# relay_board.net
KiCad netlist of a schematic drawn in EAGLE
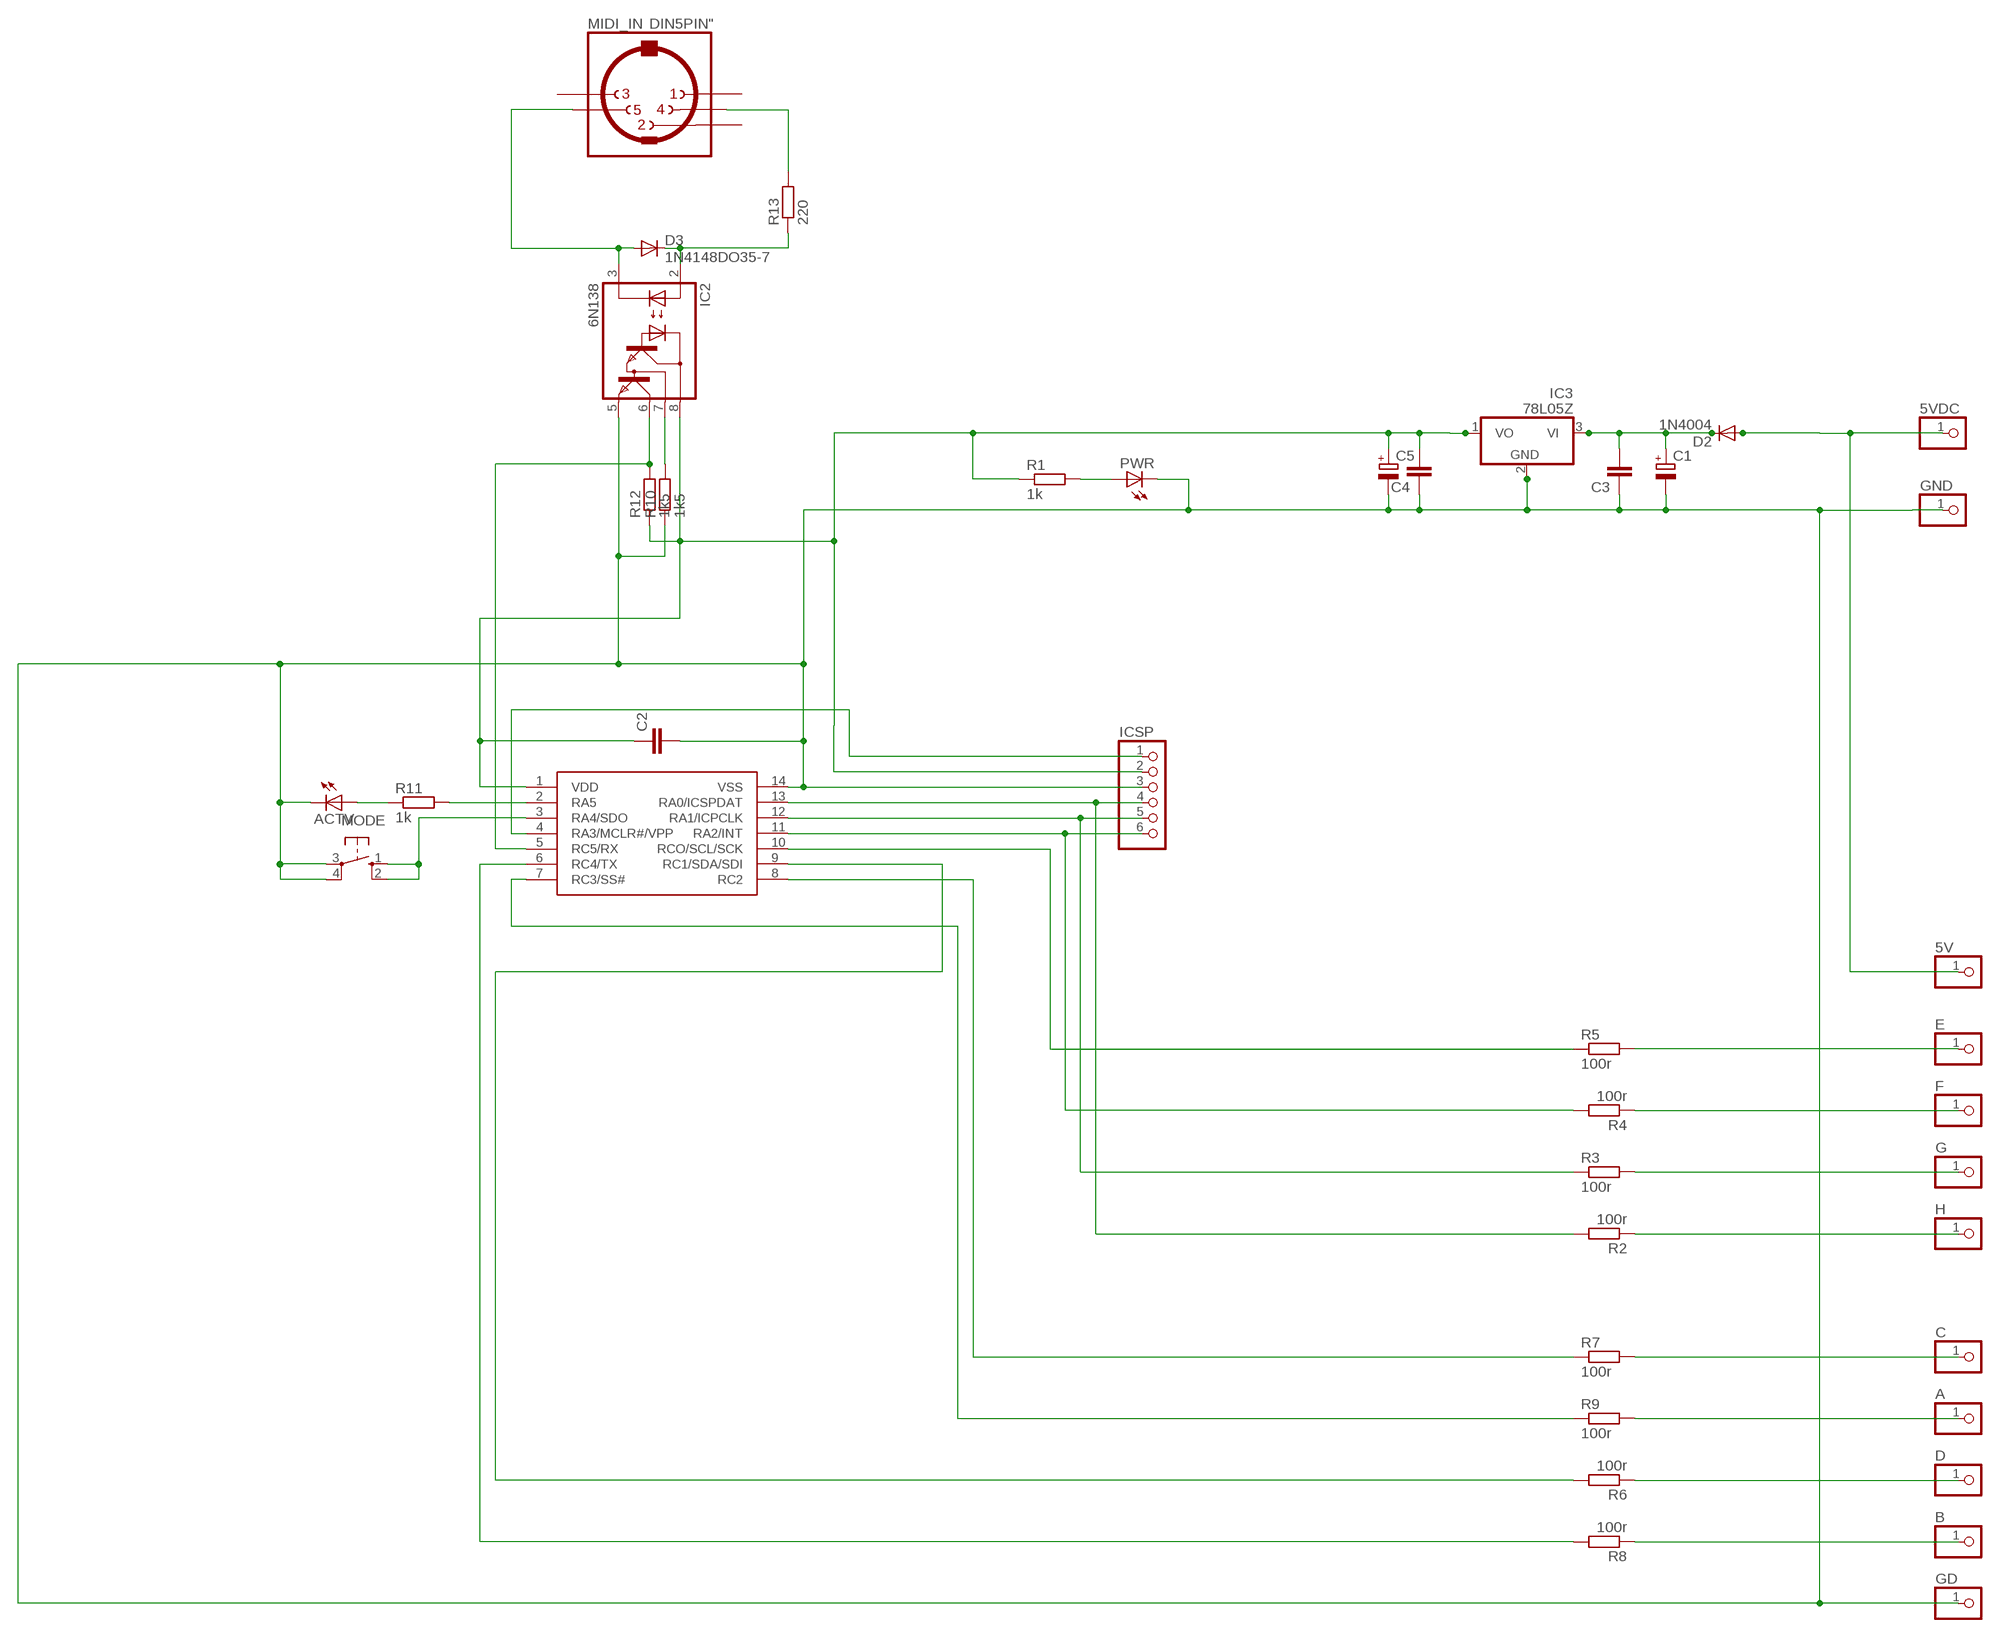
[diagram p0: schematic, sheet 1]

(export (version "E")
  (design (tool "Eeschema 10.0.6"))
  (components
    (comp (ref "5V")
      (value "PINHD-1X1")
      (footprint "eagle-import:1X01")
      (libsource (lib "eagle-import") (part "PINHD-1X1"))
    )
    (comp (ref "5VDC")
      (value "PINHD-1X1")
      (footprint "eagle-import:1X01")
      (libsource (lib "eagle-import") (part "PINHD-1X1"))
    )
    (comp (ref "A")
      (value "PINHD-1X1")
      (footprint "eagle-import:1X01")
      (libsource (lib "eagle-import") (part "PINHD-1X1"))
    )
    (comp (ref "ACTV")
      (value "LED3MM")
      (footprint "eagle-import:LED3MM")
      (libsource (lib "eagle-import") (part "LED3MM"))
    )
    (comp (ref "B")
      (value "PINHD-1X1")
      (footprint "eagle-import:1X01")
      (libsource (lib "eagle-import") (part "PINHD-1X1"))
    )
    (comp (ref "C")
      (value "PINHD-1X1")
      (footprint "eagle-import:1X01")
      (libsource (lib "eagle-import") (part "PINHD-1X1"))
    )
    (comp (ref "C1")
      (value "CPOL-EUE2.5-7")
      (footprint "eagle-import:E2,5-7")
      (libsource (lib "eagle-import") (part "CPOL-EUE2.5-7"))
    )
    (comp (ref "C2")
      (value "C2.5/2")
      (footprint "eagle-import:C2.5-2")
      (libsource (lib "eagle-import") (part "C2.5/2"))
    )
    (comp (ref "C3")
      (value "C2.5/2")
      (footprint "eagle-import:C2.5-2")
      (libsource (lib "eagle-import") (part "C2.5/2"))
    )
    (comp (ref "C4")
      (value "C2.5/2")
      (footprint "eagle-import:C2.5-2")
      (libsource (lib "eagle-import") (part "C2.5/2"))
    )
    (comp (ref "C5")
      (value "CPOL-EUE2-5")
      (footprint "eagle-import:E2-5")
      (libsource (lib "eagle-import") (part "CPOL-EUE2-5"))
    )
    (comp (ref "D")
      (value "PINHD-1X1")
      (footprint "eagle-import:1X01")
      (libsource (lib "eagle-import") (part "PINHD-1X1"))
    )
    (comp (ref "D2")
      (value "1N4004")
      (footprint "eagle-import:DO-VERT")
      (libsource (lib "eagle-import") (part "1N4004"))
    )
    (comp (ref "D3")
      (value "1N4148DO35-7")
      (footprint "eagle-import:DO35-7")
      (libsource (lib "eagle-import") (part "1N4148DO35-7"))
    )
    (comp (ref "E")
      (value "PINHD-1X1")
      (footprint "eagle-import:1X01")
      (libsource (lib "eagle-import") (part "PINHD-1X1"))
    )
    (comp (ref "F")
      (value "PINHD-1X1")
      (footprint "eagle-import:1X01")
      (libsource (lib "eagle-import") (part "PINHD-1X1"))
    )
    (comp (ref "G")
      (value "PINHD-1X1")
      (footprint "eagle-import:1X01")
      (libsource (lib "eagle-import") (part "PINHD-1X1"))
    )
    (comp (ref "GD")
      (value "PINHD-1X1")
      (footprint "eagle-import:1X01")
      (libsource (lib "eagle-import") (part "PINHD-1X1"))
    )
    (comp (ref "GND")
      (value "PINHD-1X1")
      (footprint "eagle-import:1X01")
      (libsource (lib "eagle-import") (part "PINHD-1X1"))
    )
    (comp (ref "H")
      (value "PINHD-1X1")
      (footprint "eagle-import:1X01")
      (libsource (lib "eagle-import") (part "PINHD-1X1"))
    )
    (comp (ref "IC1")
      (value "PIC16F1825DIL14")
      (footprint "eagle-import:DIL14")
      (libsource (lib "eagle-import") (part "PIC16F1825DIL14"))
    )
    (comp (ref "IC2")
      (value "6N138")
      (footprint "eagle-import:DIL08")
      (libsource (lib "eagle-import") (part "6N138"))
    )
    (comp (ref "IC3")
      (value "78L05Z")
      (footprint "eagle-import:TO92")
      (libsource (lib "eagle-import") (part "78ZL05"))
    )
    (comp (ref "ICSP")
      (value "HEADER-1X6")
      (footprint "eagle-import:1X06_OVAL")
      (libsource (lib "eagle-import") (part "HEADER-1X6"))
    )
    (comp (ref "MIDI_IN")
      (value "DIN5PIN\"")
      (footprint "eagle-import:TRUCONN90")
      (libsource (lib "eagle-import") (part "DIN5PIN{dblquote}"))
    )
    (comp (ref "MODE")
      (value "10-XX")
      (footprint "eagle-import:B3F-10XX")
      (libsource (lib "eagle-import") (part "10-XX"))
    )
    (comp (ref "PWR")
      (value "LED3MM")
      (footprint "eagle-import:LED3MM")
      (libsource (lib "eagle-import") (part "LED3MM"))
    )
    (comp (ref "R1")
      (value "1k")
      (footprint "eagle-import:0207_2V")
      (libsource (lib "eagle-import") (part "R-EU_0207/2V"))
    )
    (comp (ref "R2")
      (value "100r")
      (footprint "eagle-import:0207_2V")
      (libsource (lib "eagle-import") (part "R-EU_0207/2V"))
    )
    (comp (ref "R3")
      (value "100r")
      (footprint "eagle-import:0207_2V")
      (libsource (lib "eagle-import") (part "R-EU_0207/2V"))
    )
    (comp (ref "R4")
      (value "100r")
      (footprint "eagle-import:0207_2V")
      (libsource (lib "eagle-import") (part "R-EU_0207/2V"))
    )
    (comp (ref "R5")
      (value "100r")
      (footprint "eagle-import:0207_2V")
      (libsource (lib "eagle-import") (part "R-EU_0207/2V"))
    )
    (comp (ref "R6")
      (value "100r")
      (footprint "eagle-import:0207_2V")
      (libsource (lib "eagle-import") (part "R-EU_0207/2V"))
    )
    (comp (ref "R7")
      (value "100r")
      (footprint "eagle-import:0207_2V")
      (libsource (lib "eagle-import") (part "R-EU_0207/2V"))
    )
    (comp (ref "R8")
      (value "100r")
      (footprint "eagle-import:0207_2V")
      (libsource (lib "eagle-import") (part "R-EU_0207/2V"))
    )
    (comp (ref "R9")
      (value "100r")
      (footprint "eagle-import:0207_2V")
      (libsource (lib "eagle-import") (part "R-EU_0207/2V"))
    )
    (comp (ref "R10")
      (value "1k5")
      (footprint "eagle-import:0207_2V")
      (libsource (lib "eagle-import") (part "R-EU_0207/2V"))
    )
    (comp (ref "R11")
      (value "1k")
      (footprint "eagle-import:0207_2V")
      (libsource (lib "eagle-import") (part "R-EU_0207/2V"))
    )
    (comp (ref "R12")
      (value "1k5")
      (footprint "eagle-import:0207_2V")
      (libsource (lib "eagle-import") (part "R-EU_0207/2V"))
    )
    (comp (ref "R13")
      (value "220")
      (footprint "eagle-import:0207_7")
      (libsource (lib "eagle-import") (part "R-EU_0207/7"))
    )
  )
  (nets
    (net (code "1") (name "Net-(5V-Pad1)") (class "Default")
      (node (ref "5V") (pin "1") (pinfunction "1_1") (pintype "passive"))
      (node (ref "5VDC") (pin "1") (pinfunction "1_1") (pintype "passive"))
      (node (ref "D2") (pin "A") (pinfunction "A_A") (pintype "passive"))
    )
    (net (code "2") (name "Net-(A-Pad1)") (class "Default")
      (node (ref "A") (pin "1") (pinfunction "1_1") (pintype "passive"))
      (node (ref "R9") (pin "2") (pinfunction "2_2") (pintype "passive"))
    )
    (net (code "3") (name "Net-(ACTV-C)") (class "Default")
      (node (ref "ACTV") (pin "K") (pinfunction "C_K") (pintype "passive"))
      (node (ref "C1") (pin "-") (pinfunction "-_-") (pintype "passive"))
      (node (ref "C2") (pin "2") (pinfunction "2_2") (pintype "passive"))
      (node (ref "C3") (pin "1") (pinfunction "1_1") (pintype "passive"))
      (node (ref "C4") (pin "1") (pinfunction "1_1") (pintype "passive"))
      (node (ref "C5") (pin "-") (pinfunction "-_-") (pintype "passive"))
      (node (ref "GD") (pin "1") (pinfunction "1_1") (pintype "passive"))
      (node (ref "GND") (pin "1") (pinfunction "1_1") (pintype "passive"))
      (node (ref "IC1") (pin "14") (pinfunction "VSS_14") (pintype "power_in"))
      (node (ref "IC2") (pin "5") (pinfunction "GND_5") (pintype "passive"))
      (node (ref "IC3") (pin "2") (pinfunction "GND_2") (pintype "passive"))
      (node (ref "ICSP") (pin "3") (pinfunction "3_3") (pintype "passive"))
      (node (ref "MODE") (pin "3") (pinfunction "P_3") (pintype "passive"))
      (node (ref "MODE") (pin "4") (pinfunction "P1_4") (pintype "passive"))
      (node (ref "PWR") (pin "K") (pinfunction "C_K") (pintype "passive"))
      (node (ref "R10") (pin "1") (pinfunction "1_1") (pintype "passive"))
    )
    (net (code "4") (name "Net-(ACTV-PadA)") (class "Default")
      (node (ref "ACTV") (pin "A") (pinfunction "A_A") (pintype "passive"))
      (node (ref "R11") (pin "1") (pinfunction "1_1") (pintype "passive"))
    )
    (net (code "5") (name "Net-(B-Pad1)") (class "Default")
      (node (ref "B") (pin "1") (pinfunction "1_1") (pintype "passive"))
      (node (ref "R8") (pin "1") (pinfunction "1_1") (pintype "passive"))
    )
    (net (code "6") (name "Net-(C-Pad1)") (class "Default")
      (node (ref "C") (pin "1") (pinfunction "1_1") (pintype "passive"))
      (node (ref "R7") (pin "2") (pinfunction "2_2") (pintype "passive"))
    )
    (net (code "7") (name "Net-(D-Pad1)") (class "Default")
      (node (ref "D") (pin "1") (pinfunction "1_1") (pintype "passive"))
      (node (ref "R6") (pin "1") (pinfunction "1_1") (pintype "passive"))
    )
    (net (code "8") (name "Net-(E-Pad1)") (class "Default")
      (node (ref "E") (pin "1") (pinfunction "1_1") (pintype "passive"))
      (node (ref "R5") (pin "2") (pinfunction "2_2") (pintype "passive"))
    )
    (net (code "9") (name "Net-(F-Pad1)") (class "Default")
      (node (ref "F") (pin "1") (pinfunction "1_1") (pintype "passive"))
      (node (ref "R4") (pin "1") (pinfunction "1_1") (pintype "passive"))
    )
    (net (code "10") (name "Net-(G-Pad1)") (class "Default")
      (node (ref "G") (pin "1") (pinfunction "1_1") (pintype "passive"))
      (node (ref "R3") (pin "2") (pinfunction "2_2") (pintype "passive"))
    )
    (net (code "11") (name "Net-(H-Pad1)") (class "Default")
      (node (ref "H") (pin "1") (pinfunction "1_1") (pintype "passive"))
      (node (ref "R2") (pin "1") (pinfunction "1_1") (pintype "passive"))
    )
    (net (code "12") (name "Net-(IC1-RA0{slash}ICSPDAT)") (class "Default")
      (node (ref "IC1") (pin "13") (pinfunction "RA0/ICSPDAT_13") (pintype "bidirectional"))
      (node (ref "ICSP") (pin "4") (pinfunction "4_4") (pintype "passive"))
      (node (ref "R2") (pin "2") (pinfunction "2_2") (pintype "passive"))
    )
    (net (code "13") (name "Net-(IC1-RA1{slash}ICPCLK)") (class "Default")
      (node (ref "IC1") (pin "12") (pinfunction "RA1/ICPCLK_12") (pintype "bidirectional"))
      (node (ref "ICSP") (pin "5") (pinfunction "5_5") (pintype "passive"))
      (node (ref "R3") (pin "1") (pinfunction "1_1") (pintype "passive"))
    )
    (net (code "14") (name "Net-(IC1-RA2{slash}INT)") (class "Default")
      (node (ref "IC1") (pin "11") (pinfunction "RA2/INT_11") (pintype "bidirectional"))
      (node (ref "ICSP") (pin "6") (pinfunction "6_6") (pintype "passive"))
      (node (ref "R4") (pin "2") (pinfunction "2_2") (pintype "passive"))
    )
    (net (code "15") (name "Net-(IC1-RA3{slash}MCLR#{slash}VPP)") (class "Default")
      (node (ref "IC1") (pin "4") (pinfunction "RA3/MCLR#/VPP_4") (pintype "input"))
      (node (ref "ICSP") (pin "1") (pinfunction "1_1") (pintype "passive"))
    )
    (net (code "16") (name "Net-(IC1-RA4{slash}SDO)") (class "Default")
      (node (ref "IC1") (pin "3") (pinfunction "RA4/SDO_3") (pintype "bidirectional"))
      (node (ref "MODE") (pin "1") (pinfunction "S_1") (pintype "passive"))
      (node (ref "MODE") (pin "2") (pinfunction "S1_2") (pintype "passive"))
    )
    (net (code "17") (name "Net-(IC1-RA5)") (class "Default")
      (node (ref "IC1") (pin "2") (pinfunction "RA5_2") (pintype "bidirectional"))
      (node (ref "R11") (pin "2") (pinfunction "2_2") (pintype "passive"))
    )
    (net (code "18") (name "Net-(IC1-RC1{slash}SDA{slash}SDI)") (class "Default")
      (node (ref "IC1") (pin "9") (pinfunction "RC1/SDA/SDI_9") (pintype "bidirectional"))
      (node (ref "R6") (pin "2") (pinfunction "2_2") (pintype "passive"))
    )
    (net (code "19") (name "Net-(IC1-RC2)") (class "Default")
      (node (ref "IC1") (pin "8") (pinfunction "RC2_8") (pintype "bidirectional"))
      (node (ref "R7") (pin "1") (pinfunction "1_1") (pintype "passive"))
    )
    (net (code "20") (name "Net-(IC1-RC3{slash}SS#)") (class "Default")
      (node (ref "IC1") (pin "7") (pinfunction "RC3/SS#_7") (pintype "bidirectional"))
      (node (ref "R9") (pin "1") (pinfunction "1_1") (pintype "passive"))
    )
    (net (code "21") (name "Net-(IC1-RC4{slash}TX)") (class "Default")
      (node (ref "IC1") (pin "6") (pinfunction "RC4/TX_6") (pintype "bidirectional"))
      (node (ref "R8") (pin "2") (pinfunction "2_2") (pintype "passive"))
    )
    (net (code "22") (name "Net-(IC1-RC5{slash}RX)") (class "Default")
      (node (ref "IC1") (pin "5") (pinfunction "RC5/RX_5") (pintype "bidirectional"))
      (node (ref "IC2") (pin "6") (pinfunction "VO_6") (pintype "passive"))
      (node (ref "R12") (pin "2") (pinfunction "2_2") (pintype "passive"))
    )
    (net (code "23") (name "Net-(IC1-RCO{slash}SCL{slash}SCK)") (class "Default")
      (node (ref "IC1") (pin "10") (pinfunction "RCO/SCL/SCK_10") (pintype "bidirectional"))
      (node (ref "R5") (pin "1") (pinfunction "1_1") (pintype "passive"))
    )
    (net (code "24") (name "Net-(IC1-VDD)") (class "Default")
      (node (ref "C2") (pin "1") (pinfunction "1_1") (pintype "passive"))
      (node (ref "C4") (pin "2") (pinfunction "2_2") (pintype "passive"))
      (node (ref "C5") (pin "+") (pinfunction "+_+") (pintype "passive"))
      (node (ref "IC1") (pin "1") (pinfunction "VDD_1") (pintype "power_in"))
      (node (ref "IC2") (pin "8") (pinfunction "VCC_8") (pintype "passive"))
      (node (ref "IC3") (pin "1") (pinfunction "VO_1") (pintype "passive"))
      (node (ref "ICSP") (pin "2") (pinfunction "2_2") (pintype "passive"))
      (node (ref "R1") (pin "1") (pinfunction "1_1") (pintype "passive"))
      (node (ref "R12") (pin "1") (pinfunction "1_1") (pintype "passive"))
    )
    (net (code "25") (name "Net-(IC2-A)") (class "Default")
      (node (ref "D3") (pin "C") (pinfunction "C_C") (pintype "passive"))
      (node (ref "IC2") (pin "2") (pinfunction "A_2") (pintype "passive"))
      (node (ref "R13") (pin "1") (pinfunction "1_1") (pintype "passive"))
    )
    (net (code "26") (name "Net-(IC2-C)") (class "Default")
      (node (ref "D3") (pin "A") (pinfunction "A_A") (pintype "passive"))
      (node (ref "IC2") (pin "3") (pinfunction "C_3") (pintype "passive"))
      (node (ref "MIDI_IN") (pin "5") (pinfunction "5_5") (pintype "passive"))
    )
    (net (code "27") (name "Net-(IC2-VB)") (class "Default")
      (node (ref "IC2") (pin "7") (pinfunction "VB_7") (pintype "passive"))
      (node (ref "R10") (pin "2") (pinfunction "2_2") (pintype "passive"))
    )
    (net (code "28") (name "Net-(IC3-VI)") (class "Default")
      (node (ref "C1") (pin "+") (pinfunction "+_+") (pintype "passive"))
      (node (ref "C3") (pin "2") (pinfunction "2_2") (pintype "passive"))
      (node (ref "D2") (pin "C") (pinfunction "C_C") (pintype "passive"))
      (node (ref "IC3") (pin "3") (pinfunction "VI_3") (pintype "input"))
    )
    (net (code "29") (name "Net-(MIDI_IN-Pad4)") (class "Default")
      (node (ref "MIDI_IN") (pin "4") (pinfunction "4_4") (pintype "passive"))
      (node (ref "R13") (pin "2") (pinfunction "2_2") (pintype "passive"))
    )
    (net (code "30") (name "Net-(PWR-PadA)") (class "Default")
      (node (ref "PWR") (pin "A") (pinfunction "A_A") (pintype "passive"))
      (node (ref "R1") (pin "2") (pinfunction "2_2") (pintype "passive"))
    )
    (net (code "31") (name "unconnected-(MIDI_IN-Pad1)") (class "Default")
      (node (ref "MIDI_IN") (pin "1") (pinfunction "1_1") (pintype "passive"))
    )
    (net (code "32") (name "unconnected-(MIDI_IN-Pad2)") (class "Default")
      (node (ref "MIDI_IN") (pin "2") (pinfunction "2_2") (pintype "passive"))
    )
    (net (code "33") (name "unconnected-(MIDI_IN-Pad3)") (class "Default")
      (node (ref "MIDI_IN") (pin "3") (pinfunction "3_3") (pintype "passive"))
    )
  )
)
